# Transeiver.net
KiCad netlist of a schematic drawn in Altium Designer
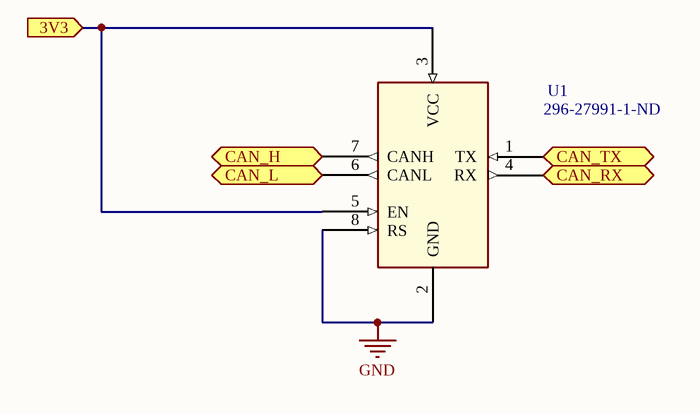
[diagram p0: Transeiver.SchDoc]

(export (version "E")
  (design (tool "Eeschema 10.0.6"))
  (components
    (comp (ref "U1")
      (value "SN65HVD234")
      (footprint "SN65HVD234DR")
      (description "IC CAN TRANSCEIVER 3.3V 8-SOIC")
      (fields
        (field (name "SUPPLIER PART NUMBER 1") "296-27991-1-ND")
        (field (name "MANUFACTURER PART NUMBER") "SN65HVD234DR")
      )
      (libsource (lib "ICs") (part "SN65HVD234"))
    )
  )
  (nets
    (net (code "1") (name "/3V3") (class "Default")
      (node (ref "U1") (pin "3") (pinfunction "VCC_3") (pintype "input"))
      (node (ref "U1") (pin "5") (pinfunction "EN_5") (pintype "input"))
    )
    (net (code "2") (name "/CAN_H") (class "Default")
      (node (ref "U1") (pin "7") (pinfunction "CANH_7") (pintype "output"))
    )
    (net (code "3") (name "/CAN_L") (class "Default")
      (node (ref "U1") (pin "6") (pinfunction "CANL_6") (pintype "output"))
    )
    (net (code "4") (name "/CAN_RX") (class "Default")
      (node (ref "U1") (pin "4") (pinfunction "RX_4") (pintype "output"))
    )
    (net (code "5") (name "/CAN_TX") (class "Default")
      (node (ref "U1") (pin "1") (pinfunction "TX_1") (pintype "input"))
    )
    (net (code "6") (name "GND") (class "Default")
      (node (ref "U1") (pin "2") (pinfunction "GND_2") (pintype "power_in"))
      (node (ref "U1") (pin "8") (pinfunction "RS_8") (pintype "input"))
    )
  )
)
